# LED.net
KiCad netlist of a schematic drawn in Altium Designer
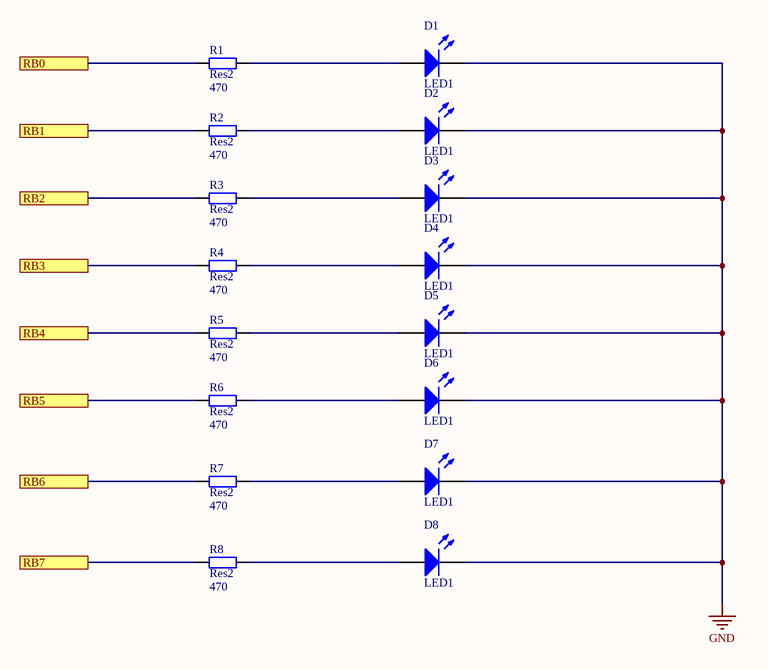
[diagram p0: LED .SchDoc]

(export (version "E")
  (design (tool "Eeschema 10.0.6"))
  (components
    (comp (ref "D1")
      (value "LED1")
      (footprint "LED-1")
      (description "Typical RED GaAs LED")
      (fields (field (name "PUBLISHER") "Altium Limited"))
      (libsource (lib "Miscellaneous Devices") (part "LED1"))
    )
    (comp (ref "D2")
      (value "LED1")
      (footprint "LED-1")
      (description "Typical RED GaAs LED")
      (fields (field (name "PUBLISHER") "Altium Limited"))
      (libsource (lib "Miscellaneous Devices") (part "LED1"))
    )
    (comp (ref "D3")
      (value "LED1")
      (footprint "LED-1")
      (description "Typical RED GaAs LED")
      (fields (field (name "PUBLISHER") "Altium Limited"))
      (libsource (lib "Miscellaneous Devices") (part "LED1"))
    )
    (comp (ref "D4")
      (value "LED1")
      (footprint "LED-1")
      (description "Typical RED GaAs LED")
      (fields (field (name "PUBLISHER") "Altium Limited"))
      (libsource (lib "Miscellaneous Devices") (part "LED1"))
    )
    (comp (ref "D5")
      (value "LED1")
      (footprint "LED-1")
      (description "Typical RED GaAs LED")
      (fields (field (name "PUBLISHER") "Altium Limited"))
      (libsource (lib "Miscellaneous Devices") (part "LED1"))
    )
    (comp (ref "D6")
      (value "LED1")
      (footprint "LED-1")
      (description "Typical RED GaAs LED")
      (fields (field (name "PUBLISHER") "Altium Limited"))
      (libsource (lib "Miscellaneous Devices") (part "LED1"))
    )
    (comp (ref "D7")
      (value "LED1")
      (footprint "LED-1")
      (description "Typical RED GaAs LED")
      (fields (field (name "PUBLISHER") "Altium Limited"))
      (libsource (lib "Miscellaneous Devices") (part "LED1"))
    )
    (comp (ref "D8")
      (value "LED1")
      (footprint "LED-1")
      (description "Typical RED GaAs LED")
      (fields (field (name "PUBLISHER") "Altium Limited"))
      (libsource (lib "Miscellaneous Devices") (part "LED1"))
    )
    (comp (ref "R1")
      (value "Res2")
      (footprint "AXIAL-0.4")
      (description "Resistor")
      (fields (field (name "ALTIUM_VALUE") "470") (field (name "PUBLISHER") "Altium Limited"))
      (libsource (lib "Miscellaneous Devices") (part "Res2"))
    )
    (comp (ref "R2")
      (value "Res2")
      (footprint "AXIAL-0.4")
      (description "Resistor")
      (fields (field (name "ALTIUM_VALUE") "470") (field (name "PUBLISHER") "Altium Limited"))
      (libsource (lib "Miscellaneous Devices") (part "Res2"))
    )
    (comp (ref "R3")
      (value "Res2")
      (footprint "AXIAL-0.4")
      (description "Resistor")
      (fields (field (name "ALTIUM_VALUE") "470") (field (name "PUBLISHER") "Altium Limited"))
      (libsource (lib "Miscellaneous Devices") (part "Res2"))
    )
    (comp (ref "R4")
      (value "Res2")
      (footprint "AXIAL-0.4")
      (description "Resistor")
      (fields (field (name "ALTIUM_VALUE") "470") (field (name "PUBLISHER") "Altium Limited"))
      (libsource (lib "Miscellaneous Devices") (part "Res2"))
    )
    (comp (ref "R5")
      (value "Res2")
      (footprint "AXIAL-0.4")
      (description "Resistor")
      (fields (field (name "ALTIUM_VALUE") "470") (field (name "PUBLISHER") "Altium Limited"))
      (libsource (lib "Miscellaneous Devices") (part "Res2"))
    )
    (comp (ref "R6")
      (value "Res2")
      (footprint "AXIAL-0.4")
      (description "Resistor")
      (fields (field (name "ALTIUM_VALUE") "470") (field (name "PUBLISHER") "Altium Limited"))
      (libsource (lib "Miscellaneous Devices") (part "Res2"))
    )
    (comp (ref "R7")
      (value "Res2")
      (footprint "AXIAL-0.4")
      (description "Resistor")
      (fields (field (name "ALTIUM_VALUE") "470") (field (name "PUBLISHER") "Altium Limited"))
      (libsource (lib "Miscellaneous Devices") (part "Res2"))
    )
    (comp (ref "R8")
      (value "Res2")
      (footprint "AXIAL-0.4")
      (description "Resistor")
      (fields (field (name "ALTIUM_VALUE") "470") (field (name "PUBLISHER") "Altium Limited"))
      (libsource (lib "Miscellaneous Devices") (part "Res2"))
    )
  )
  (nets
    (net (code "1") (name "/RB0") (class "Default")
      (node (ref "R1") (pin "1") (pinfunction "1_1") (pintype "passive"))
    )
    (net (code "2") (name "/RB1") (class "Default")
      (node (ref "R2") (pin "1") (pinfunction "1_1") (pintype "passive"))
    )
    (net (code "3") (name "/RB2") (class "Default")
      (node (ref "R3") (pin "1") (pinfunction "1_1") (pintype "passive"))
    )
    (net (code "4") (name "/RB3") (class "Default")
      (node (ref "R4") (pin "1") (pinfunction "1_1") (pintype "passive"))
    )
    (net (code "5") (name "/RB4") (class "Default")
      (node (ref "R5") (pin "1") (pinfunction "1_1") (pintype "passive"))
    )
    (net (code "6") (name "/RB5") (class "Default")
      (node (ref "R6") (pin "1") (pinfunction "1_1") (pintype "passive"))
    )
    (net (code "7") (name "/RB6") (class "Default")
      (node (ref "R7") (pin "1") (pinfunction "1_1") (pintype "passive"))
    )
    (net (code "8") (name "/RB7") (class "Default")
      (node (ref "R8") (pin "1") (pinfunction "1_1") (pintype "passive"))
    )
    (net (code "9") (name "GND") (class "Default")
      (node (ref "D1") (pin "2") (pinfunction "K_2") (pintype "passive"))
      (node (ref "D2") (pin "2") (pinfunction "K_2") (pintype "passive"))
      (node (ref "D3") (pin "2") (pinfunction "K_2") (pintype "passive"))
      (node (ref "D4") (pin "2") (pinfunction "K_2") (pintype "passive"))
      (node (ref "D5") (pin "2") (pinfunction "K_2") (pintype "passive"))
      (node (ref "D6") (pin "2") (pinfunction "K_2") (pintype "passive"))
      (node (ref "D7") (pin "2") (pinfunction "K_2") (pintype "passive"))
      (node (ref "D8") (pin "2") (pinfunction "K_2") (pintype "passive"))
    )
    (net (code "10") (name "Net-(D1-A)") (class "Default")
      (node (ref "D1") (pin "1") (pinfunction "A_1") (pintype "passive"))
      (node (ref "R1") (pin "2") (pinfunction "2_2") (pintype "passive"))
    )
    (net (code "11") (name "Net-(D2-A)") (class "Default")
      (node (ref "D2") (pin "1") (pinfunction "A_1") (pintype "passive"))
      (node (ref "R2") (pin "2") (pinfunction "2_2") (pintype "passive"))
    )
    (net (code "12") (name "Net-(D3-A)") (class "Default")
      (node (ref "D3") (pin "1") (pinfunction "A_1") (pintype "passive"))
      (node (ref "R3") (pin "2") (pinfunction "2_2") (pintype "passive"))
    )
    (net (code "13") (name "Net-(D4-A)") (class "Default")
      (node (ref "D4") (pin "1") (pinfunction "A_1") (pintype "passive"))
      (node (ref "R4") (pin "2") (pinfunction "2_2") (pintype "passive"))
    )
    (net (code "14") (name "Net-(D5-A)") (class "Default")
      (node (ref "D5") (pin "1") (pinfunction "A_1") (pintype "passive"))
      (node (ref "R5") (pin "2") (pinfunction "2_2") (pintype "passive"))
    )
    (net (code "15") (name "Net-(D6-A)") (class "Default")
      (node (ref "D6") (pin "1") (pinfunction "A_1") (pintype "passive"))
      (node (ref "R6") (pin "2") (pinfunction "2_2") (pintype "passive"))
    )
    (net (code "16") (name "Net-(D7-A)") (class "Default")
      (node (ref "D7") (pin "1") (pinfunction "A_1") (pintype "passive"))
      (node (ref "R7") (pin "2") (pinfunction "2_2") (pintype "passive"))
    )
    (net (code "17") (name "Net-(D8-A)") (class "Default")
      (node (ref "D8") (pin "1") (pinfunction "A_1") (pintype "passive"))
      (node (ref "R8") (pin "2") (pinfunction "2_2") (pintype "passive"))
    )
  )
)
